# p2_mcu.net
KiCad netlist of a schematic drawn in Altium Designer
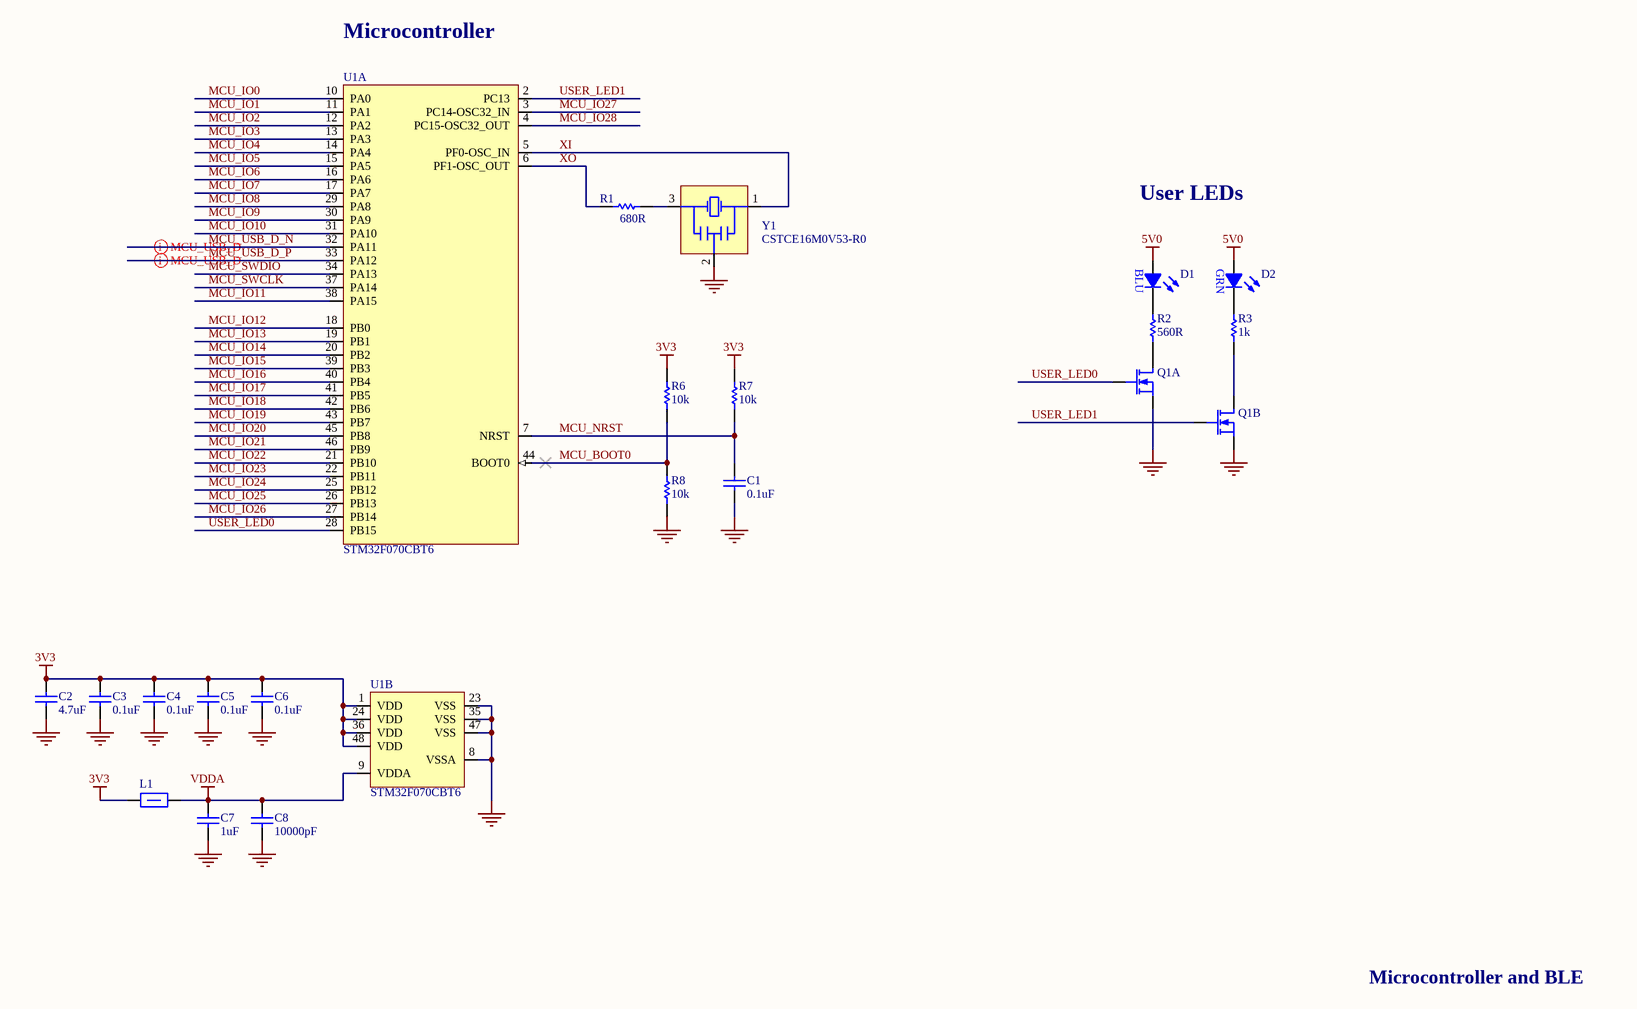
[diagram p0: p2_mcu.SchDoc]

(export (version "E")
  (design (tool "Eeschema 10.0.6"))
  (components
    (comp (ref "C1")
      (value "0.1uF")
      (footprint "C0201")
      (description "CAP CER 0.1UF 16V X5R 0201")
      (fields
        (field (name "MANUFACTURER") "Murata")
        (field (name "MANUFACTURER PART NUMBER") "GRM033R61C104ME84D")
      )
      (libsource (lib "Capacitors") (part "0.1uF 16V 0201"))
    )
    (comp (ref "C2")
      (value "4.7uF")
      (footprint "C0402")
      (description "CAP CER 4.7UF 16V X5R 0402")
      (fields
        (field (name "MANUFACTURER") "Samsung")
        (field (name "MANUFACTURER PART NUMBER") "CL05A475MO5NUNC")
      )
      (libsource (lib "Capacitors") (part "4.7uF 16V 0402"))
    )
    (comp (ref "C3")
      (value "0.1uF")
      (footprint "C0201")
      (description "CAP CER 0.1UF 16V X5R 0201")
      (fields
        (field (name "MANUFACTURER") "Murata")
        (field (name "MANUFACTURER PART NUMBER") "GRM033R61C104ME84D")
      )
      (libsource (lib "Capacitors") (part "0.1uF 16V 0201"))
    )
    (comp (ref "C4")
      (value "0.1uF")
      (footprint "C0201")
      (description "CAP CER 0.1UF 16V X5R 0201")
      (fields
        (field (name "MANUFACTURER") "Murata")
        (field (name "MANUFACTURER PART NUMBER") "GRM033R61C104ME84D")
      )
      (libsource (lib "Capacitors") (part "0.1uF 16V 0201"))
    )
    (comp (ref "C5")
      (value "0.1uF")
      (footprint "C0201")
      (description "CAP CER 0.1UF 16V X5R 0201")
      (fields
        (field (name "MANUFACTURER") "Murata")
        (field (name "MANUFACTURER PART NUMBER") "GRM033R61C104ME84D")
      )
      (libsource (lib "Capacitors") (part "0.1uF 16V 0201"))
    )
    (comp (ref "C6")
      (value "0.1uF")
      (footprint "C0201")
      (description "CAP CER 0.1UF 16V X5R 0201")
      (fields
        (field (name "MANUFACTURER") "Murata")
        (field (name "MANUFACTURER PART NUMBER") "GRM033R61C104ME84D")
      )
      (libsource (lib "Capacitors") (part "0.1uF 16V 0201"))
    )
    (comp (ref "C7")
      (value "1uF")
      (footprint "C0402")
      (description "CAP CER 1UF 25V X5R 0402")
      (fields
        (field (name "MANUFACTURER") "Taiyo Yuden")
        (field (name "MANUFACTURER PART NUMBER") "TMK105BJ105MV-F")
      )
      (libsource (lib "Capacitors") (part "1uF 25V 0402"))
    )
    (comp (ref "C8")
      (value "10000pF")
      (footprint "C0201")
      (description "CAP CER 10000PF 25V X5R 0201")
      (fields
        (field (name "MANUFACTURER") "Murata")
        (field (name "MANUFACTURER PART NUMBER") "GRM033R61E103MA12D")
      )
      (libsource (lib "Capacitors") (part "10000pF 25V 0201"))
    )
    (comp (ref "D1")
      (value "5988091107F")
      (footprint "LED0603")
      (description "LED BLUE CLEAR 0603 SMD")
      (fields
        (field (name "MANUFACTURER") "Dialight")
        (field (name "MANUFACTURER PART NUMBER") "598-8091-107F")
      )
      (libsource (lib "Diodes") (part "Blue 0603 LED"))
    )
    (comp (ref "D2")
      (value "5988070107F")
      (footprint "LED0603")
      (description "LED GREEN CLEAR 0603 SMD")
      (fields
        (field (name "MANUFACTURER") "Dialight")
        (field (name "MANUFACTURER PART NUMBER") "598-8070-107F")
      )
      (libsource (lib "Diodes") (part "Green 0603 LED"))
    )
    (comp (ref "L1")
      (value "BLM15AG601SN1D")
      (footprint "L0402")
      (description "FERRITE BEAD 600 OHM 0402 1LN")
      (fields (field (name "MANUFACTURER") "Murata") (field (name "TOLERANCE") "25%"))
      (libsource (lib "Inductors") (part "BLM15AG601SN1D"))
    )
    (comp (ref "Q1")
      (value "PMDXB600UNE")
      (footprint "NXP_DFN1010B-6")
      (description "MOSFET 2N-CH 20V 0.6A 6DFN")
      (fields (field (name "MANUFACTURER") "NXP Semiconductors"))
      (libsource (lib "ICs") (part "PMDXB600UNE"))
    )
    (comp (ref "R1")
      (value "680R")
      (footprint "R0201")
      (description "RES SMD 680 OHM 1% 1/20W 0201")
      (fields
        (field (name "MANUFACTURER") "Yageo")
        (field (name "MANUFACTURER PART NUMBER") "RC0201FR-07680RL")
      )
      (libsource (lib "Resistors") (part "680R 0201"))
    )
    (comp (ref "R2")
      (value "560R")
      (footprint "R0201")
      (description "RES SMD 560 OHM 1% 1/20W 0201")
      (fields
        (field (name "MANUFACTURER") "Panasonic ECG")
        (field (name "MANUFACTURER PART NUMBER") "ERJ-1GEF5600C")
      )
      (libsource (lib "Resistors") (part "560R 0201"))
    )
    (comp (ref "R3")
      (value "1k")
      (footprint "R0201")
      (description "RES SMD 1K OHM 1% 1/20W 0201")
      (fields
        (field (name "MANUFACTURER") "Panasonic ECG")
        (field (name "MANUFACTURER PART NUMBER") "ERJ-1GEF1001C")
      )
      (libsource (lib "Resistors") (part "1k 0201"))
    )
    (comp (ref "R6")
      (value "10k")
      (footprint "R0201")
      (description "RES SMD 10K OHM 1% 1/20W 0201")
      (fields
        (field (name "MANUFACTURER") "Panasonic ECG")
        (field (name "MANUFACTURER PART NUMBER") "ERJ-1GEF1002C")
      )
      (libsource (lib "Resistors") (part "10k 0201"))
    )
    (comp (ref "R7")
      (value "10k")
      (footprint "R0201")
      (description "RES SMD 10K OHM 1% 1/20W 0201")
      (fields
        (field (name "MANUFACTURER") "Panasonic ECG")
        (field (name "MANUFACTURER PART NUMBER") "ERJ-1GEF1002C")
      )
      (libsource (lib "Resistors") (part "10k 0201"))
    )
    (comp (ref "R8")
      (value "10k")
      (footprint "R0201")
      (description "RES SMD 10K OHM 1% 1/20W 0201")
      (fields
        (field (name "MANUFACTURER") "Panasonic ECG")
        (field (name "MANUFACTURER PART NUMBER") "ERJ-1GEF1002C")
      )
      (libsource (lib "Resistors") (part "10k 0201"))
    )
    (comp (ref "U1")
      (value "STM32F070CBT6")
      (footprint "STM_LQFP48")
      (description "IC MCU 32BIT 128KB FLASH 48LQFP")
      (fields (field (name "MANUFACTURER") "STMicroelectronics"))
      (libsource (lib "ICs") (part "STM32F070CBT6"))
    )
    (comp (ref "Y1")
      (value "CSTCE16M0V53-R0")
      (footprint "MUR_CSTCE_V")
      (description "CER RES 16.0000MHZ 15PF SMD")
      (fields (field (name "MANUFACTURER") "Murata") (field (name "TOLERANCE") "0.5%"))
      (libsource (lib "Oscillators") (part "16MHz Resonator"))
    )
  )
  (nets
    (net (code "1") (name "/MCU_BOOT0") (class "Default")
      (node (ref "R6") (pin "1") (pinfunction "1_1") (pintype "passive"))
      (node (ref "R8") (pin "2") (pinfunction "2_2") (pintype "passive"))
      (node (ref "U1") (pin "44") (pinfunction "BOOT0_44") (pintype "input"))
    )
    (net (code "2") (name "/MCU_IO0") (class "Default")
      (node (ref "U1") (pin "10") (pinfunction "PA0_10") (pintype "bidirectional"))
    )
    (net (code "3") (name "/MCU_IO1") (class "Default")
      (node (ref "U1") (pin "11") (pinfunction "PA1_11") (pintype "bidirectional"))
    )
    (net (code "4") (name "/MCU_IO2") (class "Default")
      (node (ref "U1") (pin "12") (pinfunction "PA2_12") (pintype "bidirectional"))
    )
    (net (code "5") (name "/MCU_IO3") (class "Default")
      (node (ref "U1") (pin "13") (pinfunction "PA3_13") (pintype "bidirectional"))
    )
    (net (code "6") (name "/MCU_IO4") (class "Default")
      (node (ref "U1") (pin "14") (pinfunction "PA4_14") (pintype "bidirectional"))
    )
    (net (code "7") (name "/MCU_IO5") (class "Default")
      (node (ref "U1") (pin "15") (pinfunction "PA5_15") (pintype "bidirectional"))
    )
    (net (code "8") (name "/MCU_IO6") (class "Default")
      (node (ref "U1") (pin "16") (pinfunction "PA6_16") (pintype "bidirectional"))
    )
    (net (code "9") (name "/MCU_IO7") (class "Default")
      (node (ref "U1") (pin "17") (pinfunction "PA7_17") (pintype "bidirectional"))
    )
    (net (code "10") (name "/MCU_IO8") (class "Default")
      (node (ref "U1") (pin "29") (pinfunction "PA8_29") (pintype "bidirectional"))
    )
    (net (code "11") (name "/MCU_IO9") (class "Default")
      (node (ref "U1") (pin "30") (pinfunction "PA9_30") (pintype "bidirectional"))
    )
    (net (code "12") (name "/MCU_IO10") (class "Default")
      (node (ref "U1") (pin "31") (pinfunction "PA10_31") (pintype "bidirectional"))
    )
    (net (code "13") (name "/MCU_IO11") (class "Default")
      (node (ref "U1") (pin "38") (pinfunction "PA15_38") (pintype "bidirectional"))
    )
    (net (code "14") (name "/MCU_IO12") (class "Default")
      (node (ref "U1") (pin "18") (pinfunction "PB0_18") (pintype "bidirectional"))
    )
    (net (code "15") (name "/MCU_IO13") (class "Default")
      (node (ref "U1") (pin "19") (pinfunction "PB1_19") (pintype "bidirectional"))
    )
    (net (code "16") (name "/MCU_IO14") (class "Default")
      (node (ref "U1") (pin "20") (pinfunction "PB2_20") (pintype "bidirectional"))
    )
    (net (code "17") (name "/MCU_IO15") (class "Default")
      (node (ref "U1") (pin "39") (pinfunction "PB3_39") (pintype "bidirectional"))
    )
    (net (code "18") (name "/MCU_IO16") (class "Default")
      (node (ref "U1") (pin "40") (pinfunction "PB4_40") (pintype "bidirectional"))
    )
    (net (code "19") (name "/MCU_IO17") (class "Default")
      (node (ref "U1") (pin "41") (pinfunction "PB5_41") (pintype "bidirectional"))
    )
    (net (code "20") (name "/MCU_IO18") (class "Default")
      (node (ref "U1") (pin "42") (pinfunction "PB6_42") (pintype "bidirectional"))
    )
    (net (code "21") (name "/MCU_IO19") (class "Default")
      (node (ref "U1") (pin "43") (pinfunction "PB7_43") (pintype "bidirectional"))
    )
    (net (code "22") (name "/MCU_IO20") (class "Default")
      (node (ref "U1") (pin "45") (pinfunction "PB8_45") (pintype "bidirectional"))
    )
    (net (code "23") (name "/MCU_IO21") (class "Default")
      (node (ref "U1") (pin "46") (pinfunction "PB9_46") (pintype "bidirectional"))
    )
    (net (code "24") (name "/MCU_IO22") (class "Default")
      (node (ref "U1") (pin "21") (pinfunction "PB10_21") (pintype "bidirectional"))
    )
    (net (code "25") (name "/MCU_IO23") (class "Default")
      (node (ref "U1") (pin "22") (pinfunction "PB11_22") (pintype "bidirectional"))
    )
    (net (code "26") (name "/MCU_IO24") (class "Default")
      (node (ref "U1") (pin "25") (pinfunction "PB12_25") (pintype "bidirectional"))
    )
    (net (code "27") (name "/MCU_IO25") (class "Default")
      (node (ref "U1") (pin "26") (pinfunction "PB13_26") (pintype "bidirectional"))
    )
    (net (code "28") (name "/MCU_IO26") (class "Default")
      (node (ref "U1") (pin "27") (pinfunction "PB14_27") (pintype "bidirectional"))
    )
    (net (code "29") (name "/MCU_IO27") (class "Default")
      (node (ref "U1") (pin "3") (pinfunction "PC14-OSC32_IN_3") (pintype "bidirectional"))
    )
    (net (code "30") (name "/MCU_IO28") (class "Default")
      (node (ref "U1") (pin "4") (pinfunction "PC15-OSC32_OUT_4") (pintype "bidirectional"))
    )
    (net (code "31") (name "/MCU_NRST") (class "Default")
      (node (ref "C1") (pin "2") (pinfunction "2_2") (pintype "passive"))
      (node (ref "R7") (pin "1") (pinfunction "1_1") (pintype "passive"))
      (node (ref "U1") (pin "7") (pinfunction "NRST_7") (pintype "bidirectional"))
    )
    (net (code "32") (name "/MCU_SWCLK") (class "Default")
      (node (ref "U1") (pin "37") (pinfunction "PA14_37") (pintype "bidirectional"))
    )
    (net (code "33") (name "/MCU_SWDIO") (class "Default")
      (node (ref "U1") (pin "34") (pinfunction "PA13_34") (pintype "bidirectional"))
    )
    (net (code "34") (name "/MCU_USB_D_N") (class "Default")
      (node (ref "U1") (pin "32") (pinfunction "PA11_32") (pintype "bidirectional"))
    )
    (net (code "35") (name "/MCU_USB_D_P") (class "Default")
      (node (ref "U1") (pin "33") (pinfunction "PA12_33") (pintype "bidirectional"))
    )
    (net (code "36") (name "/USER_LED0") (class "Default")
      (node (ref "Q1") (pin "2") (pinfunction "G1_2") (pintype "passive"))
      (node (ref "U1") (pin "28") (pinfunction "PB15_28") (pintype "bidirectional"))
    )
    (net (code "37") (name "/USER_LED1") (class "Default")
      (node (ref "Q1") (pin "5") (pinfunction "G2_5") (pintype "passive"))
      (node (ref "U1") (pin "2") (pinfunction "PC13_2") (pintype "bidirectional"))
    )
    (net (code "38") (name "/XI") (class "Default")
      (node (ref "U1") (pin "5") (pinfunction "PF0-OSC_IN_5") (pintype "bidirectional"))
      (node (ref "Y1") (pin "1") (pinfunction "1_1") (pintype "passive"))
    )
    (net (code "39") (name "/XO") (class "Default")
      (node (ref "R1") (pin "1") (pinfunction "1_1") (pintype "passive"))
      (node (ref "U1") (pin "6") (pinfunction "PF1-OSC_OUT_6") (pintype "bidirectional"))
    )
    (net (code "40") (name "3V3") (class "Default")
      (node (ref "C2") (pin "2") (pinfunction "2_2") (pintype "passive"))
      (node (ref "C3") (pin "2") (pinfunction "2_2") (pintype "passive"))
      (node (ref "C4") (pin "2") (pinfunction "2_2") (pintype "passive"))
      (node (ref "C5") (pin "2") (pinfunction "2_2") (pintype "passive"))
      (node (ref "C6") (pin "2") (pinfunction "2_2") (pintype "passive"))
      (node (ref "L1") (pin "1") (pinfunction "1_1") (pintype "passive"))
      (node (ref "R6") (pin "2") (pinfunction "2_2") (pintype "passive"))
      (node (ref "R7") (pin "2") (pinfunction "2_2") (pintype "passive"))
      (node (ref "U1") (pin "1") (pinfunction "VDD_1") (pintype "power_in"))
      (node (ref "U1") (pin "24") (pinfunction "VDD_24") (pintype "power_in"))
      (node (ref "U1") (pin "36") (pinfunction "VDD_36") (pintype "power_in"))
      (node (ref "U1") (pin "48") (pinfunction "VDD_48") (pintype "power_in"))
    )
    (net (code "41") (name "5V0") (class "Default")
      (node (ref "D1") (pin "2") (pinfunction "A_2") (pintype "passive"))
      (node (ref "D2") (pin "2") (pinfunction "A_2") (pintype "passive"))
    )
    (net (code "42") (name "GND") (class "Default")
      (node (ref "C1") (pin "1") (pinfunction "1_1") (pintype "passive"))
      (node (ref "C2") (pin "1") (pinfunction "1_1") (pintype "passive"))
      (node (ref "C3") (pin "1") (pinfunction "1_1") (pintype "passive"))
      (node (ref "C4") (pin "1") (pinfunction "1_1") (pintype "passive"))
      (node (ref "C5") (pin "1") (pinfunction "1_1") (pintype "passive"))
      (node (ref "C6") (pin "1") (pinfunction "1_1") (pintype "passive"))
      (node (ref "C7") (pin "1") (pinfunction "1_1") (pintype "passive"))
      (node (ref "C8") (pin "1") (pinfunction "1_1") (pintype "passive"))
      (node (ref "Q1") (pin "1") (pinfunction "S1_1") (pintype "passive"))
      (node (ref "Q1") (pin "4") (pinfunction "S2_4") (pintype "passive"))
      (node (ref "R8") (pin "1") (pinfunction "1_1") (pintype "passive"))
      (node (ref "U1") (pin "23") (pinfunction "VSS_23") (pintype "power_in"))
      (node (ref "U1") (pin "35") (pinfunction "VSS_35") (pintype "power_in"))
      (node (ref "U1") (pin "47") (pinfunction "VSS_47") (pintype "power_in"))
      (node (ref "U1") (pin "8") (pinfunction "VSSA_8") (pintype "power_in"))
      (node (ref "Y1") (pin "2") (pinfunction "2_2") (pintype "passive"))
    )
    (net (code "43") (name "Net-(D1-K)") (class "Default")
      (node (ref "D1") (pin "1") (pinfunction "K_1") (pintype "passive"))
      (node (ref "R2") (pin "2") (pinfunction "2_2") (pintype "passive"))
    )
    (net (code "44") (name "Net-(D2-K)") (class "Default")
      (node (ref "D2") (pin "1") (pinfunction "K_1") (pintype "passive"))
      (node (ref "R3") (pin "2") (pinfunction "2_2") (pintype "passive"))
    )
    (net (code "45") (name "Net-(Q1A-D1)") (class "Default")
      (node (ref "Q1") (pin "6") (pinfunction "D1_6") (pintype "passive"))
      (node (ref "R2") (pin "1") (pinfunction "1_1") (pintype "passive"))
    )
    (net (code "46") (name "Net-(Q1B-S2-Pad3)") (class "Default")
      (node (ref "Q1") (pin "3") (pinfunction "S2_3") (pintype "passive"))
      (node (ref "R3") (pin "1") (pinfunction "1_1") (pintype "passive"))
    )
    (net (code "47") (name "Net-(R1-Pad2)") (class "Default")
      (node (ref "R1") (pin "2") (pinfunction "2_2") (pintype "passive"))
      (node (ref "Y1") (pin "3") (pinfunction "3_3") (pintype "passive"))
    )
    (net (code "48") (name "VDDA") (class "Default")
      (node (ref "C7") (pin "2") (pinfunction "2_2") (pintype "passive"))
      (node (ref "C8") (pin "2") (pinfunction "2_2") (pintype "passive"))
      (node (ref "L1") (pin "2") (pinfunction "2_2") (pintype "passive"))
      (node (ref "U1") (pin "9") (pinfunction "VDDA_9") (pintype "power_in"))
    )
  )
)
